# 06_-_SPI_I2C_devices.net
KiCad netlist of a schematic drawn in Altium Designer
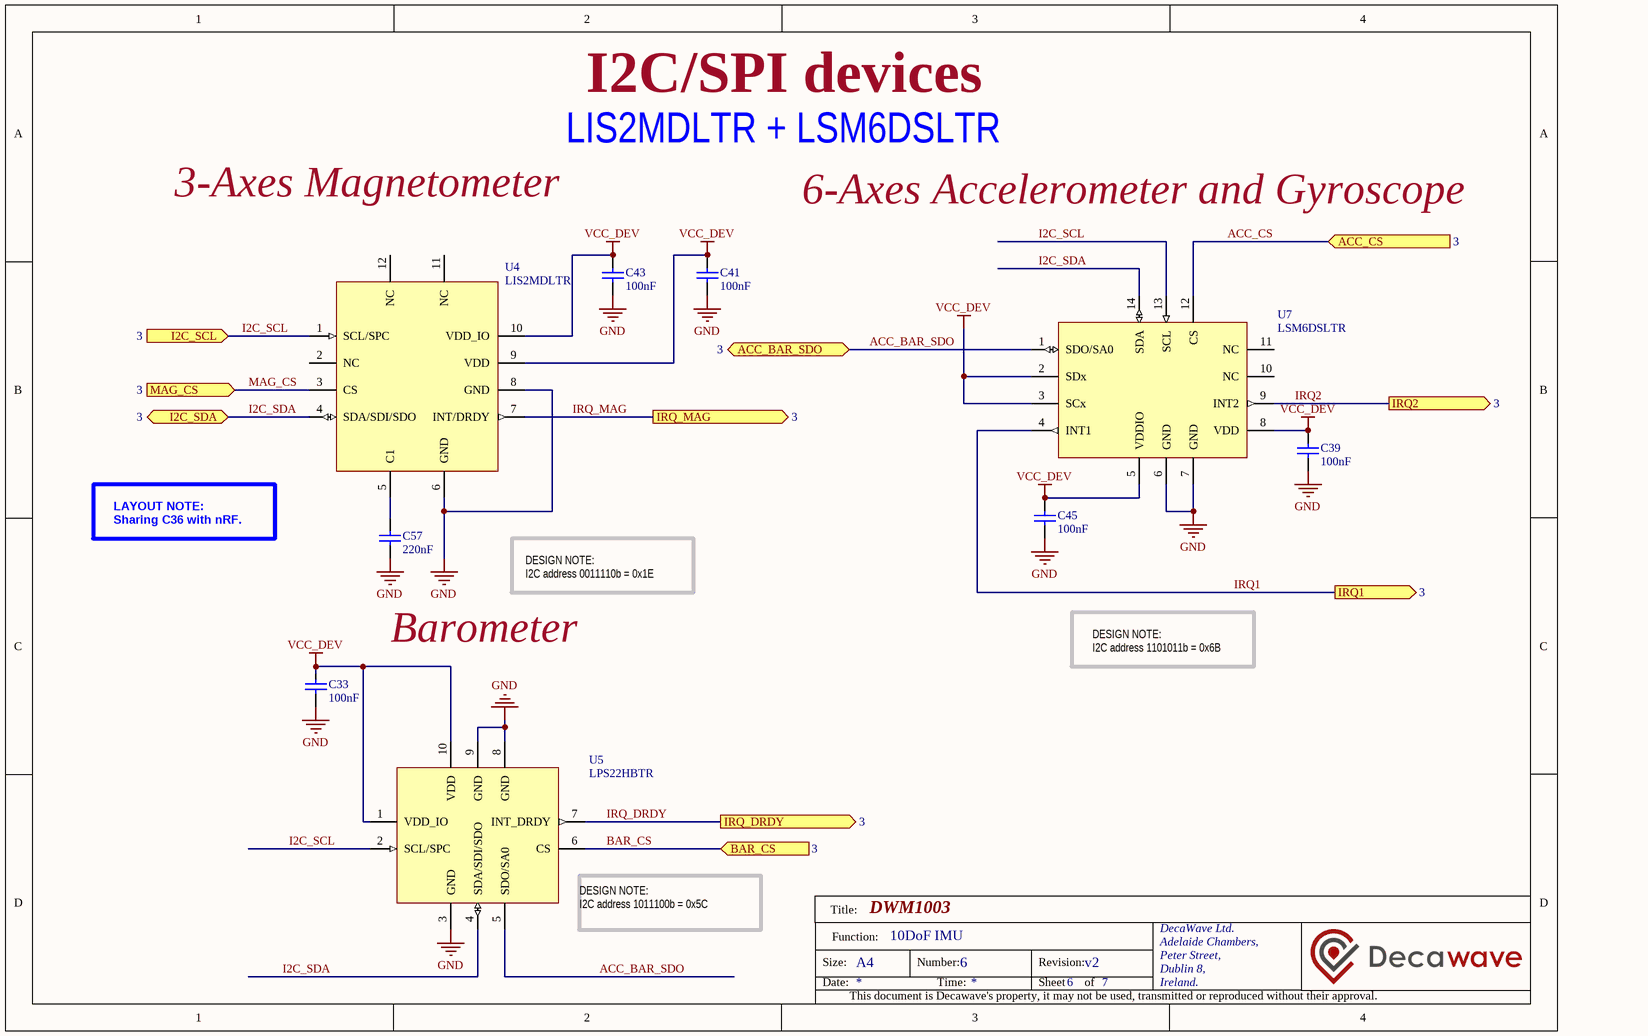
[diagram p0: [06] - SPI I2C devices.SchDoc]

(export (version "E")
  (design (tool "Eeschema 10.0.6"))
  (components
    (comp (ref "C33")
      (value "100nF")
      (footprint "C0201")
      (description "CAP CER 0.1UF 25V X6S 0201")
      (fields
        (field (name "MANUFACTURER") "Murata Electronics North America")
        (field (name "MANUFACTURER PART NUMBER") "GRM033C81E104ME14D")
      )
      (libsource (lib "drak_Library") (part "GRM033C81E104ME14D"))
    )
    (comp (ref "C39")
      (value "100nF")
      (footprint "C0201")
      (description "CAP CER 0.1UF 25V X6S 0201")
      (fields
        (field (name "MANUFACTURER") "Murata Electronics North America")
        (field (name "MANUFACTURER PART NUMBER") "GRM033C81E104ME14D")
      )
      (libsource (lib "drak_Library") (part "GRM033C81E104ME14D"))
    )
    (comp (ref "C41")
      (value "100nF")
      (footprint "C0201")
      (description "CAP CER 0.1UF 25V X6S 0201")
      (fields
        (field (name "MANUFACTURER") "Murata Electronics North America")
        (field (name "MANUFACTURER PART NUMBER") "GRM033C81E104ME14D")
      )
      (libsource (lib "drak_Library") (part "GRM033C81E104ME14D"))
    )
    (comp (ref "C43")
      (value "100nF")
      (footprint "C0201")
      (description "CAP CER 0.1UF 25V X6S 0201")
      (fields
        (field (name "MANUFACTURER") "Murata Electronics North America")
        (field (name "MANUFACTURER PART NUMBER") "GRM033C81E104ME14D")
      )
      (libsource (lib "drak_Library") (part "GRM033C81E104ME14D"))
    )
    (comp (ref "C45")
      (value "100nF")
      (footprint "C0201")
      (description "CAP CER 0.1UF 25V X6S 0201")
      (fields
        (field (name "MANUFACTURER") "Murata Electronics North America")
        (field (name "MANUFACTURER PART NUMBER") "GRM033C81E104ME14D")
      )
      (libsource (lib "drak_Library") (part "GRM033C81E104ME14D"))
    )
    (comp (ref "C57")
      (value "220nF")
      (footprint "C0201")
      (description "CAP CER 220NF 25V X6S 0201")
      (fields
        (field (name "MANUFACTURER") "Murata Electronics North America")
        (field (name "MANUFACTURER PART NUMBER") "GRM033R61A224KE90D")
      )
      (libsource (lib "drak_Library") (part "GRM033C81E104ME14D"))
    )
    (comp (ref "U4")
      (value "LIS2MDLTR")
      (footprint "IC_LGA-12")
      (fields (field (name "MANUFACTURER") "STmicroelectronics"))
      (libsource (lib "LGA12_LGA14_LIB") (part "LIS2MDL"))
    )
    (comp (ref "U5")
      (value "LPS22HBTR")
      (footprint "HLGA-10L")
      (fields (field (name "MANUFACTURER") "STmicroelectronics"))
      (libsource (lib "LGA12_LGA14_LIB") (part "LPS22HB"))
    )
    (comp (ref "U7")
      (value "LSM6DSLTR")
      (footprint "IC_LGA-14")
      (fields (field (name "MANUFACTURER") "STmicroelectronics"))
      (libsource (lib "LGA12_LGA14_LIB") (part "LSM6DSL"))
    )
  )
  (nets
    (net (code "1") (name "/ACC_BAR_SDO") (class "Default")
      (node (ref "U5") (pin "5") (pinfunction "SDO/SA0_5") (pintype "passive"))
      (node (ref "U7") (pin "1") (pinfunction "SDO/SA0_1") (pintype "bidirectional"))
    )
    (net (code "2") (name "/ACC_CS") (class "Default")
      (node (ref "U7") (pin "12") (pinfunction "CS_12") (pintype "passive"))
    )
    (net (code "3") (name "/BAR_CS") (class "Default")
      (node (ref "U5") (pin "6") (pinfunction "CS_6") (pintype "passive"))
    )
    (net (code "4") (name "/I2C_SCL") (class "Default")
      (node (ref "U4") (pin "1") (pinfunction "SCL/SPC_1") (pintype "input"))
      (node (ref "U5") (pin "2") (pinfunction "SCL/SPC_2") (pintype "input"))
      (node (ref "U7") (pin "13") (pinfunction "SCL_13") (pintype "input"))
    )
    (net (code "5") (name "/I2C_SDA") (class "Default")
      (node (ref "U4") (pin "4") (pinfunction "SDA/SDI/SDO_4") (pintype "bidirectional"))
      (node (ref "U5") (pin "4") (pinfunction "SDA/SDI/SDO_4") (pintype "bidirectional"))
      (node (ref "U7") (pin "14") (pinfunction "SDA_14") (pintype "bidirectional"))
    )
    (net (code "6") (name "/IRQ1") (class "Default")
      (node (ref "U7") (pin "4") (pinfunction "INT1_4") (pintype "output"))
    )
    (net (code "7") (name "/IRQ2") (class "Default")
      (node (ref "U7") (pin "9") (pinfunction "INT2_9") (pintype "output"))
    )
    (net (code "8") (name "/IRQ_DRDY") (class "Default")
      (node (ref "U5") (pin "7") (pinfunction "INT_DRDY_7") (pintype "output"))
    )
    (net (code "9") (name "/IRQ_MAG") (class "Default")
      (node (ref "U4") (pin "7") (pinfunction "INT/DRDY_7") (pintype "output"))
    )
    (net (code "10") (name "/MAG_CS") (class "Default")
      (node (ref "U4") (pin "3") (pinfunction "CS_3") (pintype "passive"))
    )
    (net (code "11") (name "GND") (class "Default")
      (node (ref "C33") (pin "1") (pinfunction "1_1") (pintype "passive"))
      (node (ref "C39") (pin "1") (pinfunction "1_1") (pintype "passive"))
      (node (ref "C41") (pin "1") (pinfunction "1_1") (pintype "passive"))
      (node (ref "C43") (pin "1") (pinfunction "1_1") (pintype "passive"))
      (node (ref "C45") (pin "1") (pinfunction "1_1") (pintype "passive"))
      (node (ref "C57") (pin "1") (pinfunction "1_1") (pintype "passive"))
      (node (ref "U4") (pin "6") (pinfunction "GND_6") (pintype "passive"))
      (node (ref "U4") (pin "8") (pinfunction "GND_8") (pintype "passive"))
      (node (ref "U5") (pin "3") (pinfunction "GND_3") (pintype "passive"))
      (node (ref "U5") (pin "8") (pinfunction "GND_8") (pintype "passive"))
      (node (ref "U5") (pin "9") (pinfunction "GND_9") (pintype "passive"))
      (node (ref "U7") (pin "6") (pinfunction "GND_6") (pintype "passive"))
      (node (ref "U7") (pin "7") (pinfunction "GND_7") (pintype "passive"))
    )
    (net (code "12") (name "Net-(U4-C1)") (class "Default")
      (node (ref "C57") (pin "2") (pinfunction "2_2") (pintype "passive"))
      (node (ref "U4") (pin "5") (pinfunction "C1_5") (pintype "passive"))
    )
    (net (code "13") (name "VCC_DEV") (class "Default")
      (node (ref "C33") (pin "2") (pinfunction "2_2") (pintype "passive"))
      (node (ref "C39") (pin "2") (pinfunction "2_2") (pintype "passive"))
      (node (ref "C41") (pin "2") (pinfunction "2_2") (pintype "passive"))
      (node (ref "C43") (pin "2") (pinfunction "2_2") (pintype "passive"))
      (node (ref "C45") (pin "2") (pinfunction "2_2") (pintype "passive"))
      (node (ref "U4") (pin "10") (pinfunction "VDD_IO_10") (pintype "power_in"))
      (node (ref "U4") (pin "9") (pinfunction "VDD_9") (pintype "power_in"))
      (node (ref "U5") (pin "1") (pinfunction "VDD_IO_1") (pintype "power_in"))
      (node (ref "U5") (pin "10") (pinfunction "VDD_10") (pintype "power_in"))
      (node (ref "U7") (pin "2") (pinfunction "SDx_2") (pintype "passive"))
      (node (ref "U7") (pin "3") (pinfunction "SCx_3") (pintype "passive"))
      (node (ref "U7") (pin "5") (pinfunction "VDDIO_5") (pintype "power_in"))
      (node (ref "U7") (pin "8") (pinfunction "VDD_8") (pintype "power_in"))
    )
    (net (code "14") (name "unconnected-(U4-NC-Pad2)") (class "Default")
      (node (ref "U4") (pin "2") (pinfunction "NC_2") (pintype "passive"))
    )
    (net (code "15") (name "unconnected-(U4-NC-Pad11)") (class "Default")
      (node (ref "U4") (pin "11") (pinfunction "NC_11") (pintype "passive"))
    )
    (net (code "16") (name "unconnected-(U4-NC-Pad12)") (class "Default")
      (node (ref "U4") (pin "12") (pinfunction "NC_12") (pintype "passive"))
    )
    (net (code "17") (name "unconnected-(U7-NC-Pad10)") (class "Default")
      (node (ref "U7") (pin "10") (pinfunction "NC_10") (pintype "passive"))
    )
    (net (code "18") (name "unconnected-(U7-NC-Pad11)") (class "Default")
      (node (ref "U7") (pin "11") (pinfunction "NC_11") (pintype "passive"))
    )
  )
)
